# proyecto_final.net
KiCad netlist of a schematic drawn in Altium Designer
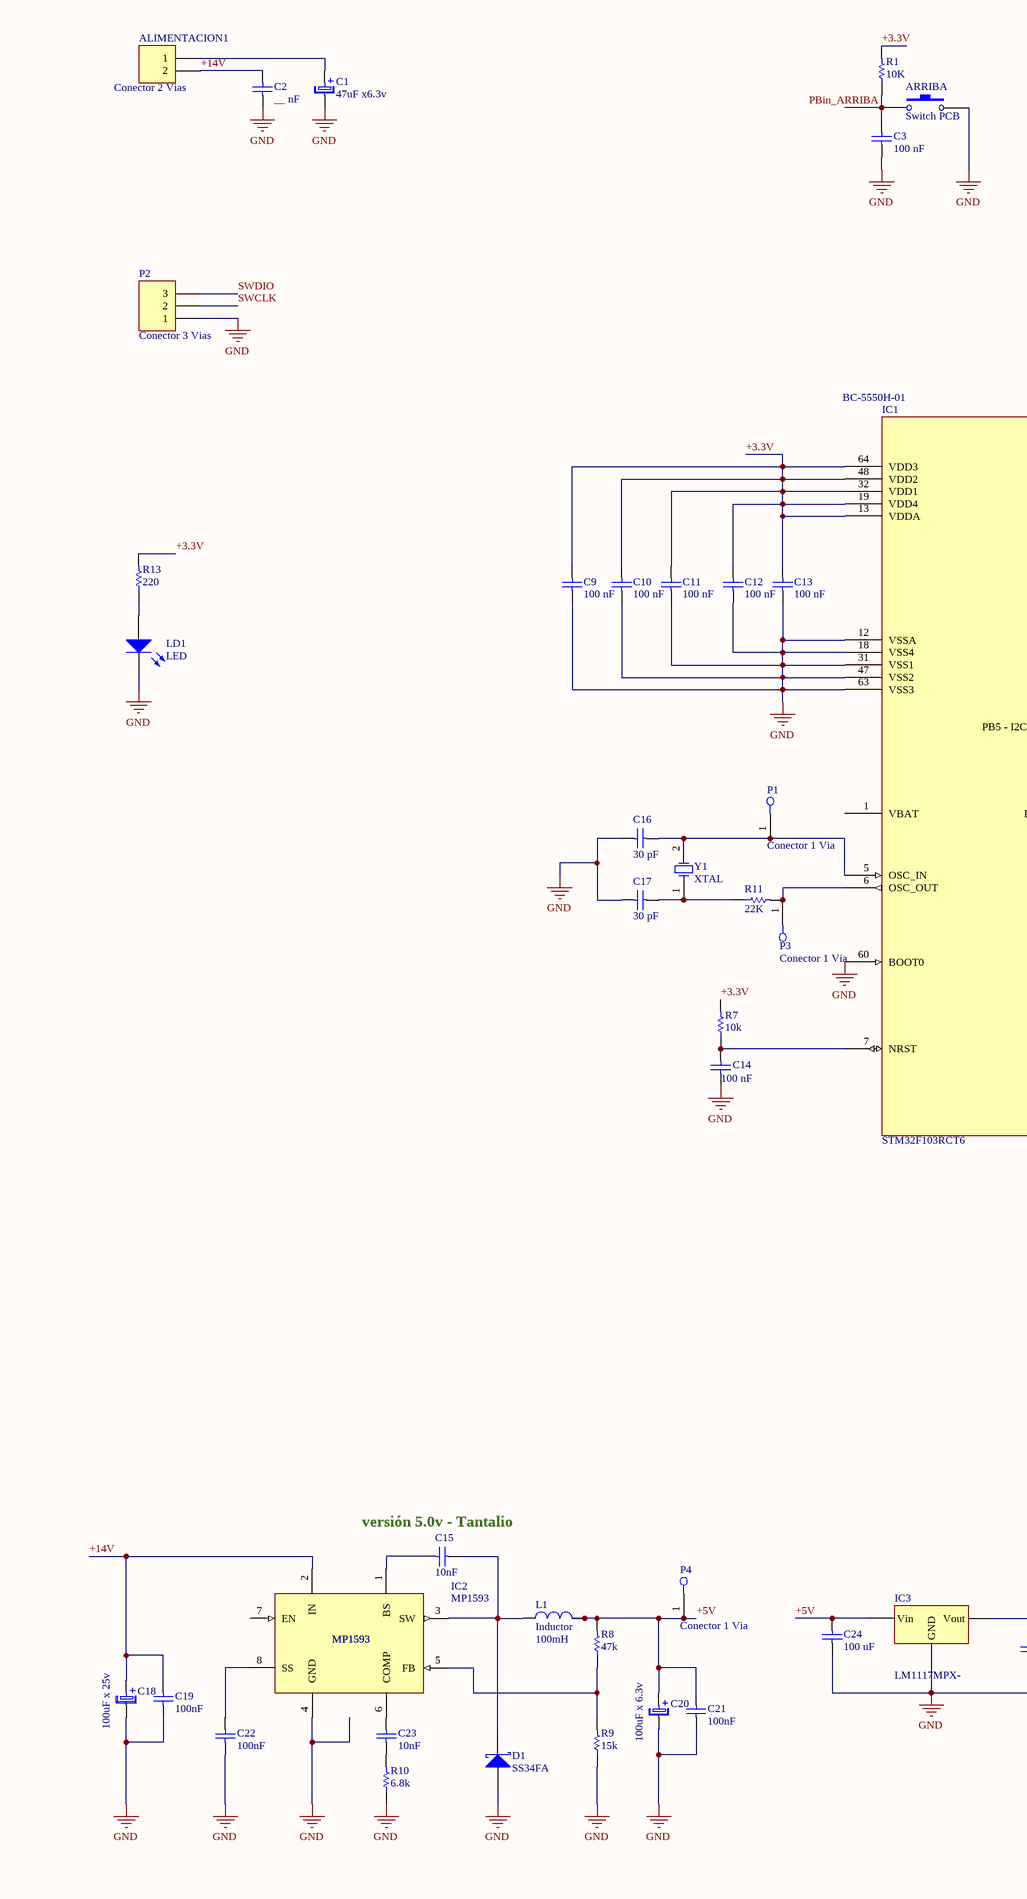
[diagram p0: proyecto final.SchDoc, left]
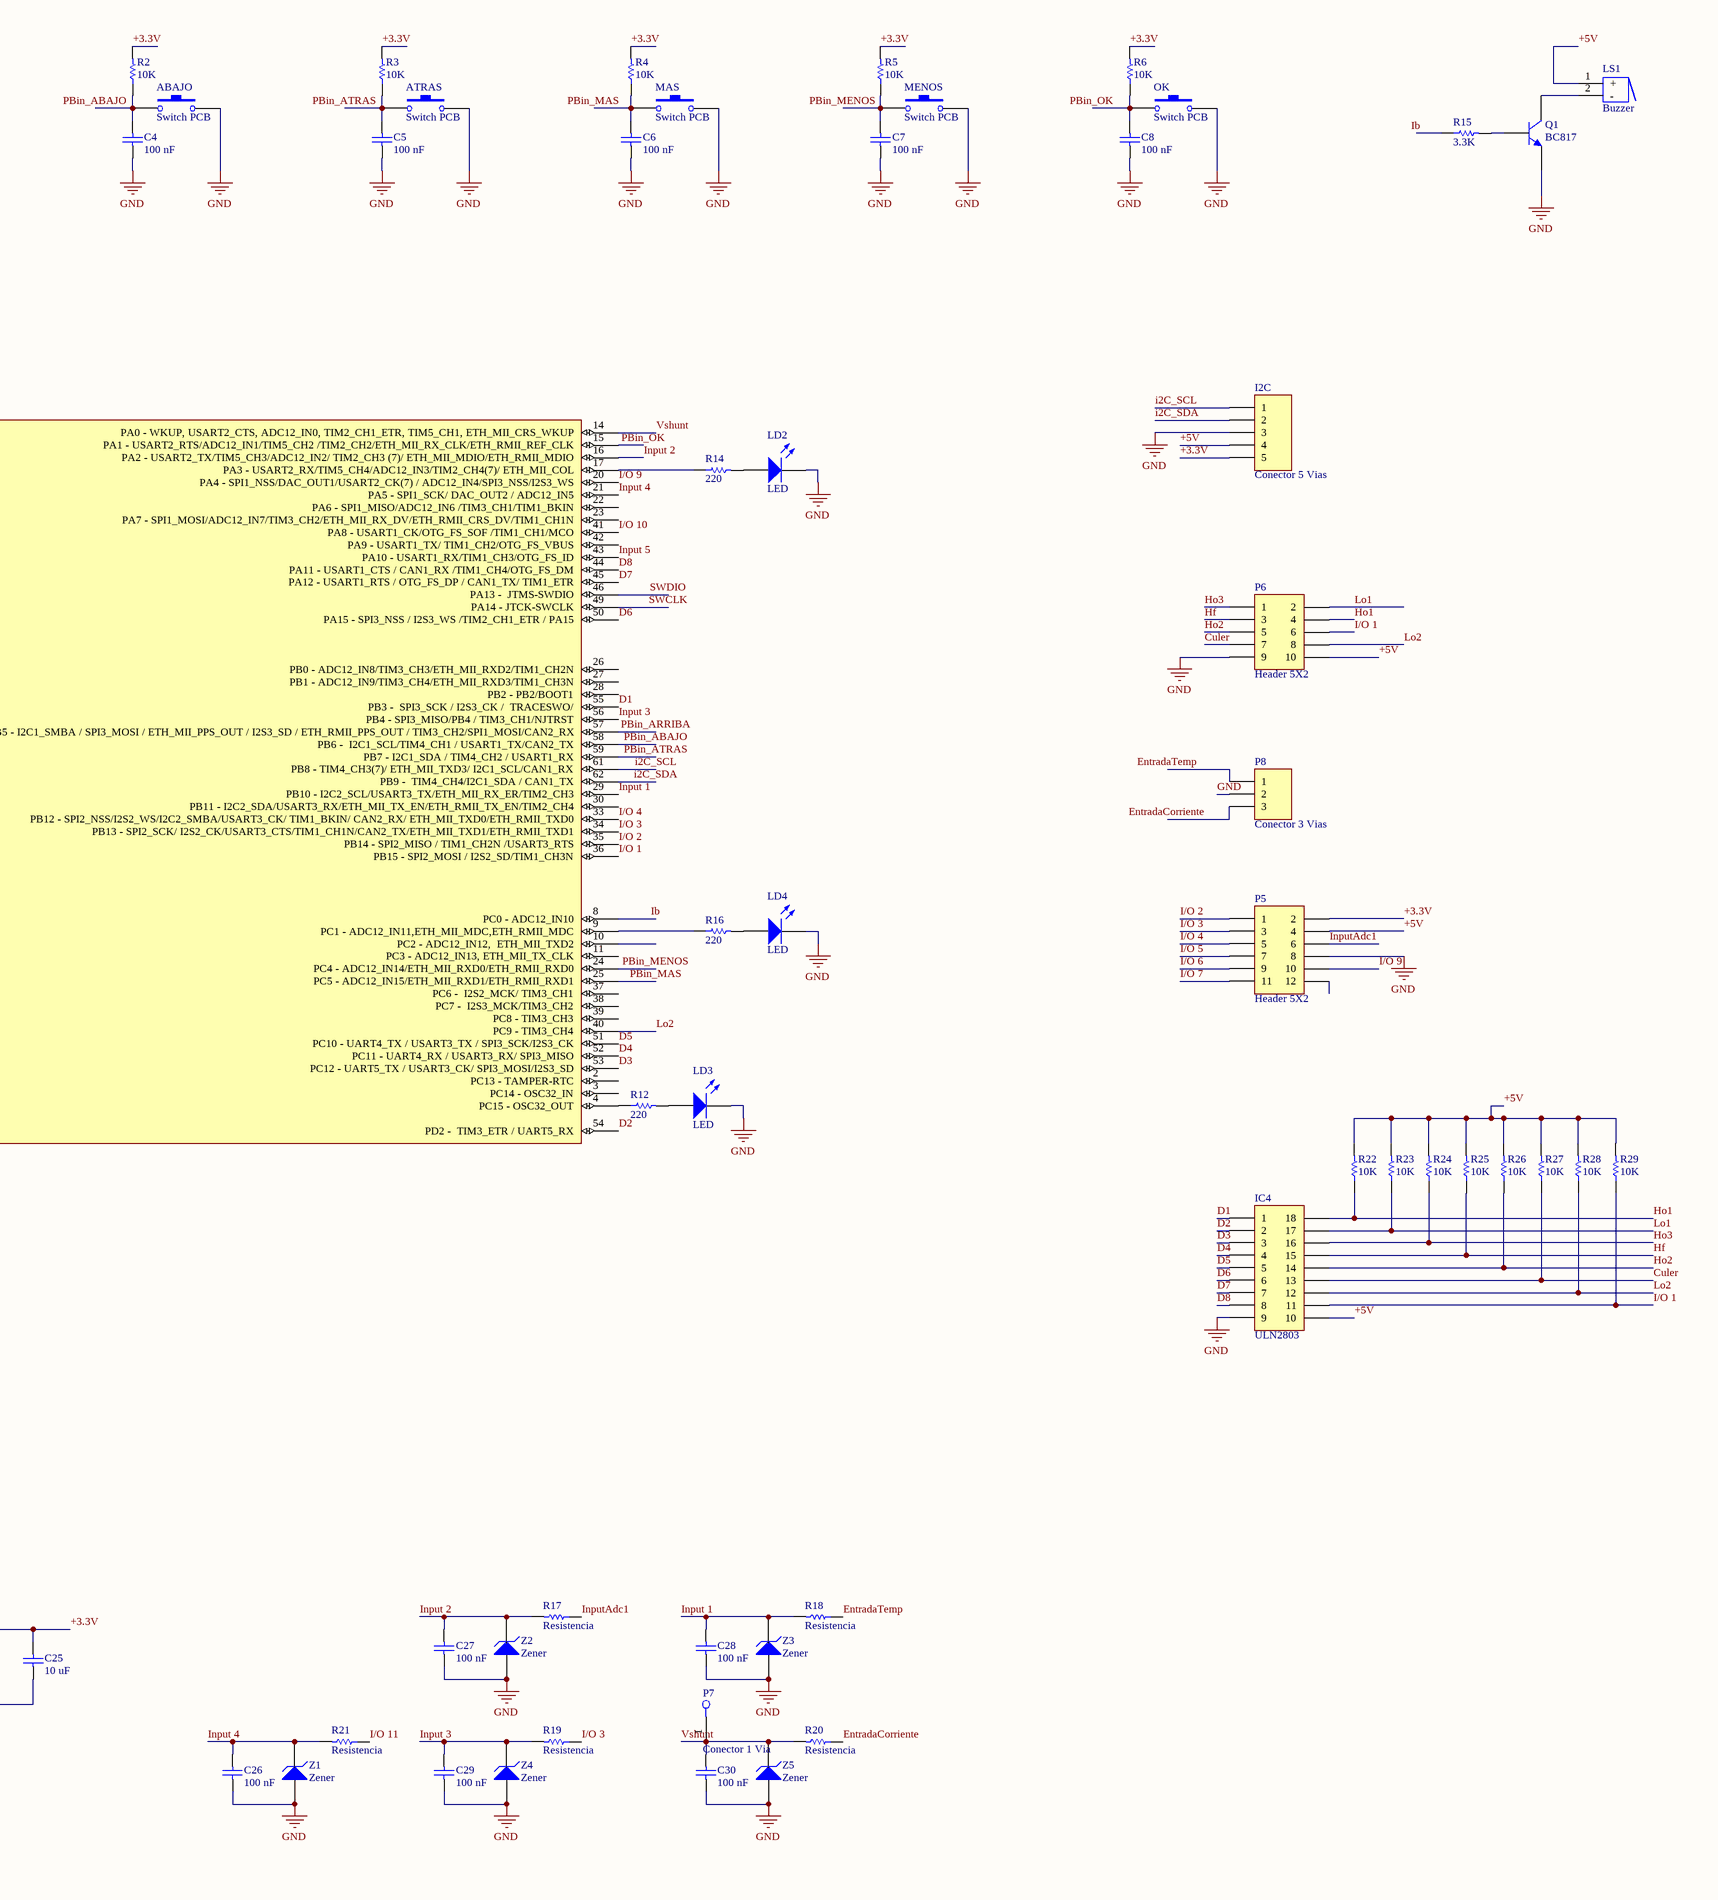
[diagram p1: proyecto final.SchDoc, right]

(export (version "E")
  (design (tool "Eeschema 10.0.6"))
  (components
    (comp (ref "ABAJO")
      (value "Switch PCB")
      (footprint "TAC SWITCH 6X6 (5MM)")
      (fields (field (name "PUBLISHER") "Altium Limited"))
      (libsource (lib "ProbIny") (part "Switch PCB"))
    )
    (comp (ref "ALIMENTACION1")
      (value "Conector 2 Vias")
      (footprint "CON 2")
      (description "Header, 2-Pin")
      (fields (field (name "PUBLISHER") "Altium Limited"))
      (libsource (lib "TORNADO LIBRERIA") (part "Header 2"))
    )
    (comp (ref "ARRIBA")
      (value "Switch PCB")
      (footprint "TAC SWITCH 6X6 (5MM)")
      (fields (field (name "PUBLISHER") "Altium Limited"))
      (libsource (lib "ProbIny") (part "Switch PCB"))
    )
    (comp (ref "ATRAS")
      (value "Switch PCB")
      (footprint "TAC SWITCH 6X6 (5MM)")
      (fields (field (name "PUBLISHER") "Altium Limited"))
      (libsource (lib "ProbIny") (part "Switch PCB"))
    )
    (comp (ref "C1")
      (value "47uF x6.3v")
      (footprint "CAP Pitch 80 - 5x11")
      (description "Capacitor Polarizado (Radial)")
      (fields (field (name "PUBLISHER") "Altium Limited"))
      (libsource (lib "TORNADO LIBRERIA") (part "Capacitor Polarizado"))
    )
    (comp (ref "C2")
      (value "__ nF")
      (footprint "C-0805")
      (description "Capacitor No Polarizado (Axial)")
      (libsource (lib "TORNADO LIBRERIA") (part "Capacitor NP"))
    )
    (comp (ref "C3")
      (value "100 nF")
      (footprint "C-0805")
      (description "Capacitor No Polarizado (Axial)")
      (libsource (lib "ProbIny") (part "Capacitor NP"))
    )
    (comp (ref "C4")
      (value "100 nF")
      (footprint "C-0805")
      (description "Capacitor No Polarizado (Axial)")
      (libsource (lib "ProbIny") (part "Capacitor NP"))
    )
    (comp (ref "C5")
      (value "100 nF")
      (footprint "C-0805")
      (description "Capacitor No Polarizado (Axial)")
      (libsource (lib "ProbIny") (part "Capacitor NP"))
    )
    (comp (ref "C6")
      (value "100 nF")
      (footprint "C-0805")
      (description "Capacitor No Polarizado (Axial)")
      (libsource (lib "ProbIny") (part "Capacitor NP"))
    )
    (comp (ref "C7")
      (value "100 nF")
      (footprint "C-0805")
      (description "Capacitor No Polarizado (Axial)")
      (libsource (lib "ProbIny") (part "Capacitor NP"))
    )
    (comp (ref "C8")
      (value "100 nF")
      (footprint "C-0805")
      (description "Capacitor No Polarizado (Axial)")
      (libsource (lib "ProbIny") (part "Capacitor NP"))
    )
    (comp (ref "C9")
      (value "100 nF")
      (footprint "C-0805")
      (description "Capacitor No Polarizado (Axial)")
      (libsource (lib "ProbIny") (part "Capacitor NP"))
    )
    (comp (ref "C10")
      (value "100 nF")
      (footprint "C-0805")
      (description "Capacitor No Polarizado (Axial)")
      (libsource (lib "ProbIny") (part "Capacitor NP"))
    )
    (comp (ref "C11")
      (value "100 nF")
      (footprint "C-0805")
      (description "Capacitor No Polarizado (Axial)")
      (libsource (lib "ProbIny") (part "Capacitor NP"))
    )
    (comp (ref "C12")
      (value "100 nF")
      (footprint "C-0805")
      (description "Capacitor No Polarizado (Axial)")
      (libsource (lib "ProbIny") (part "Capacitor NP"))
    )
    (comp (ref "C13")
      (value "100 nF")
      (footprint "C-0805")
      (description "Capacitor No Polarizado (Axial)")
      (libsource (lib "ProbIny") (part "Capacitor NP"))
    )
    (comp (ref "C14")
      (value "100 nF")
      (footprint "C-0805")
      (description "Capacitor No Polarizado (Axial)")
      (libsource (lib "TORNADO LIBRERIA") (part "Capacitor NP"))
    )
    (comp (ref "C15")
      (value "10nF")
      (footprint "C-0805")
      (description "Capacitor No Polarizado (Axial)")
      (libsource (lib "TORNADO LIBRERIA") (part "Capacitor NP"))
    )
    (comp (ref "C16")
      (value "30 pF")
      (footprint "C-0805")
      (description "Capacitor No Polarizado (Axial)")
      (libsource (lib "ProbIny") (part "Capacitor NP"))
    )
    (comp (ref "C17")
      (value "30 pF")
      (footprint "C-0805")
      (description "Capacitor No Polarizado (Axial)")
      (libsource (lib "ProbIny") (part "Capacitor NP"))
    )
    (comp (ref "C18")
      (value "100uF x 25v")
      (footprint "C-CASE-B")
      (description "Capacitor Polarizado (Radial)")
      (fields (field (name "PUBLISHER") "Altium Limited"))
      (libsource (lib "ProbIny") (part "Capacitor Polarizado"))
    )
    (comp (ref "C19")
      (value "100nF")
      (footprint "C-0805")
      (description "Capacitor No Polarizado (Axial)")
      (libsource (lib "TORNADO LIBRERIA") (part "Capacitor NP"))
    )
    (comp (ref "C20")
      (value "100uF x 6.3v")
      (footprint "C-CASE-B")
      (description "Capacitor Polarizado (Radial)")
      (fields (field (name "PUBLISHER") "Altium Limited"))
      (libsource (lib "ProbIny") (part "Capacitor Polarizado"))
    )
    (comp (ref "C21")
      (value "100nF")
      (footprint "C-0805")
      (description "Capacitor No Polarizado (Axial)")
      (libsource (lib "TORNADO LIBRERIA") (part "Capacitor NP"))
    )
    (comp (ref "C22")
      (value "100nF")
      (footprint "C-0805")
      (description "Capacitor No Polarizado (Axial)")
      (libsource (lib "TORNADO LIBRERIA") (part "Capacitor NP"))
    )
    (comp (ref "C23")
      (value "10nF")
      (footprint "C-0805")
      (description "Capacitor No Polarizado (Axial)")
      (libsource (lib "TORNADO LIBRERIA") (part "Capacitor NP"))
    )
    (comp (ref "C24")
      (value "100 uF")
      (footprint "C-0805")
      (description "Capacitor No Polarizado (Axial)")
      (libsource (lib "ProbIny") (part "Capacitor NP"))
    )
    (comp (ref "C25")
      (value "10 uF")
      (footprint "C-0805")
      (description "Capacitor No Polarizado (Axial)")
      (libsource (lib "ProbIny") (part "Capacitor NP"))
    )
    (comp (ref "C26")
      (value "100 nF")
      (footprint "C-0805")
      (description "Capacitor No Polarizado (Axial)")
      (libsource (lib "ProbIny") (part "Capacitor NP"))
    )
    (comp (ref "C27")
      (value "100 nF")
      (footprint "C-0805")
      (description "Capacitor No Polarizado (Axial)")
      (libsource (lib "ProbIny") (part "Capacitor NP"))
    )
    (comp (ref "C28")
      (value "100 nF")
      (footprint "C-0805")
      (description "Capacitor No Polarizado (Axial)")
      (libsource (lib "ProbIny") (part "Capacitor NP"))
    )
    (comp (ref "C29")
      (value "100 nF")
      (footprint "C-0805")
      (description "Capacitor No Polarizado (Axial)")
      (libsource (lib "ProbIny") (part "Capacitor NP"))
    )
    (comp (ref "C30")
      (value "100 nF")
      (footprint "C-0805")
      (description "Capacitor No Polarizado (Axial)")
      (libsource (lib "ProbIny") (part "Capacitor NP"))
    )
    (comp (ref "D1")
      (value "SS34FA")
      (footprint "SOD-123")
      (description "Diodo Schottky")
      (libsource (lib "ProbIny") (part "Diodo Schottky"))
    )
    (comp (ref "I2C")
      (value "Conector 5 Vias")
      (footprint "HEADER-V-5")
      (description "Header, 5-Pin")
      (fields (field (name "PUBLISHER") "Altium Limited"))
      (libsource (lib "ProbIny") (part "Header 5"))
    )
    (comp (ref "IC1")
      (value "STM32F103RCT6")
      (footprint "LQFP-64")
      (description "CPU M3 72MHz\r\n256k Flash\r\n2 ADC\r\n2 I2C\r\n5 USART")
      (fields (field (name "SUPPLIER PART NUMBER 1") "BC-5550H-01"))
      (libsource (lib "ProbIny") (part "STM32F103RCT6"))
    )
    (comp (ref "IC2")
      (value "MP1593")
      (footprint "SOIC-8E")
      (description "Step-Down Converter 3A, 28V, 385kHz")
      (libsource (lib "ProbIny") (part "MP1593"))
    )
    (comp (ref "IC3")
      (value "LM1117MPX-")
      (footprint "SOT-223 TERMICO")
      (libsource (lib "ProbIny") (part "LM1117MPX-"))
    )
    (comp (ref "IC4")
      (value "ULN2803")
      (footprint "SOIC-18")
      (description "Eigth darlignton array")
      (fields (field (name "PUBLISHER") "Altium Limited"))
      (libsource (lib "ProbIny") (part "ULN2803"))
    )
    (comp (ref "L1")
      (value "Inductor")
      (footprint "INDUCTOR CDRH6D28NP-100NC")
      (fields (field (name "ALTIUM_VALUE") "100mH") (field (name "PUBLISHER") "Altium Limited"))
      (libsource (lib "ProbIny") (part "Inductor"))
    )
    (comp (ref "LD1")
      (value "LED")
      (footprint "LD-0805-AZUL")
      (description "Diodo LED")
      (libsource (lib "ProbIny") (part "LED"))
    )
    (comp (ref "LD2")
      (value "LED")
      (footprint "LD-0805-AZUL")
      (description "Diodo LED")
      (libsource (lib "ProbIny") (part "LED"))
    )
    (comp (ref "LD3")
      (value "LED")
      (footprint "LD-0805-AZUL")
      (description "Diodo LED")
      (libsource (lib "ProbIny") (part "LED"))
    )
    (comp (ref "LD4")
      (value "LED")
      (footprint "LD-0805-AZUL")
      (description "Diodo LED")
      (libsource (lib "ProbIny") (part "LED"))
    )
    (comp (ref "LS1")
      (value "Buzzer")
      (footprint "BUZZER")
      (description "Magnetic Transducer Buzzer")
      (fields (field (name "PUBLISHER") "Altium Limited"))
      (libsource (lib "ProbIny") (part "Buzzer"))
    )
    (comp (ref "MAS")
      (value "Switch PCB")
      (footprint "TAC SWITCH 6X6 (5MM)")
      (fields (field (name "PUBLISHER") "Altium Limited"))
      (libsource (lib "ProbIny") (part "Switch PCB"))
    )
    (comp (ref "MENOS")
      (value "Switch PCB")
      (footprint "TAC SWITCH 6X6 (5MM)")
      (fields (field (name "PUBLISHER") "Altium Limited"))
      (libsource (lib "ProbIny") (part "Switch PCB"))
    )
    (comp (ref "OK")
      (value "Switch PCB")
      (footprint "TAC SWITCH 6X6 (5MM)")
      (fields (field (name "PUBLISHER") "Altium Limited"))
      (libsource (lib "ProbIny") (part "Switch PCB"))
    )
    (comp (ref "P1")
      (value "Conector 1 Via")
      (footprint "PAD 1.5x2.5mm")
      (description "Header, 1-Pin")
      (libsource (lib "ProbIny") (part "Header 1"))
    )
    (comp (ref "P2")
      (value "Conector 3 Vias")
      (footprint "HEADER-V-3")
      (description "Header, 3-Pin")
      (fields (field (name "PUBLISHER") "Altium Limited"))
      (libsource (lib "ProbIny") (part "Header 3"))
    )
    (comp (ref "P3")
      (value "Conector 1 Via")
      (footprint "PAD 1.5x2.5mm")
      (description "Header, 1-Pin")
      (libsource (lib "ProbIny") (part "Header 1"))
    )
    (comp (ref "P4")
      (value "Conector 1 Via")
      (footprint "PAD 1.5x2.5mm")
      (description "Header, 1-Pin")
      (libsource (lib "ProbIny") (part "Header 1"))
    )
    (comp (ref "P5")
      (value "Header 5X2")
      (footprint "HEADER 6x2")
      (description "Header, 5-Pin, Dual row")
      (fields (field (name "PUBLISHER") "Altium Limited"))
      (libsource (lib "ProbIny") (part "Header 6X2"))
    )
    (comp (ref "P6")
      (value "Header 5X2")
      (footprint "HEADER 5x2")
      (description "Header, 5-Pin, Dual row")
      (fields (field (name "PUBLISHER") "Altium Limited"))
      (libsource (lib "ProbIny") (part "Header 5X2"))
    )
    (comp (ref "P7")
      (value "Conector 1 Via")
      (footprint "PAD 1.5x2.5mm")
      (description "Header, 1-Pin")
      (libsource (lib "ProbIny") (part "Header 1"))
    )
    (comp (ref "P8")
      (value "Conector 3 Vias")
      (footprint "HEADER-V-3")
      (description "Header, 3-Pin")
      (fields (field (name "PUBLISHER") "Altium Limited"))
      (libsource (lib "") (part "Header 3_1"))
    )
    (comp (ref "Q1")
      (value "BC817")
      (footprint "SOT-23")
      (description "45 V, 500 mA NPN general-purpose transistors")
      (libsource (lib "ProbIny") (part "BC817"))
    )
    (comp (ref "R1")
      (value "10K")
      (footprint "R-0805")
      (description "Resistencia")
      (libsource (lib "ProbIny") (part "Resistencia"))
    )
    (comp (ref "R2")
      (value "10K")
      (footprint "R-0805")
      (description "Resistencia")
      (libsource (lib "ProbIny") (part "Resistencia"))
    )
    (comp (ref "R3")
      (value "10K")
      (footprint "R-0805")
      (description "Resistencia")
      (libsource (lib "ProbIny") (part "Resistencia"))
    )
    (comp (ref "R4")
      (value "10K")
      (footprint "R-0805")
      (description "Resistencia")
      (libsource (lib "ProbIny") (part "Resistencia"))
    )
    (comp (ref "R5")
      (value "10K")
      (footprint "R-0805")
      (description "Resistencia")
      (libsource (lib "ProbIny") (part "Resistencia"))
    )
    (comp (ref "R6")
      (value "10K")
      (footprint "R-0805")
      (description "Resistencia")
      (libsource (lib "ProbIny") (part "Resistencia"))
    )
    (comp (ref "R7")
      (value "10k")
      (footprint "R-0805")
      (description "Resistencia")
      (libsource (lib "TORNADO LIBRERIA") (part "Resistencia"))
    )
    (comp (ref "R8")
      (value "47k")
      (footprint "R-0805")
      (description "Resistencia")
      (libsource (lib "TORNADO LIBRERIA") (part "Resistencia"))
    )
    (comp (ref "R9")
      (value "15k")
      (footprint "R-0805")
      (description "Resistencia")
      (libsource (lib "TORNADO LIBRERIA") (part "Resistencia"))
    )
    (comp (ref "R10")
      (value "6.8k")
      (footprint "R-0805")
      (description "Resistencia")
      (libsource (lib "TORNADO LIBRERIA") (part "Resistencia"))
    )
    (comp (ref "R11")
      (value "22K")
      (footprint "R-0805")
      (description "Resistencia")
      (libsource (lib "ProbIny") (part "Resistencia"))
    )
    (comp (ref "R12")
      (value "220")
      (footprint "R-0805")
      (description "Resistencia")
      (libsource (lib "ProbIny") (part "Resistencia"))
    )
    (comp (ref "R13")
      (value "220")
      (footprint "R-0805")
      (description "Resistencia")
      (libsource (lib "ProbIny") (part "Resistencia"))
    )
    (comp (ref "R14")
      (value "220")
      (footprint "R-0805")
      (description "Resistencia")
      (libsource (lib "ProbIny") (part "Resistencia"))
    )
    (comp (ref "R15")
      (value "3.3K")
      (footprint "R-0805")
      (description "Resistencia")
      (libsource (lib "ProbIny") (part "Resistencia"))
    )
    (comp (ref "R16") (value "220") (footprint "R-0805") (libsource (lib "ProbIny") (part "Resistencia")))
    (comp (ref "R17")
      (value "Resistencia")
      (footprint "R-0805")
      (libsource (lib "ProbIny") (part "Resistencia"))
    )
    (comp (ref "R18")
      (value "Resistencia")
      (footprint "R-0805")
      (libsource (lib "ProbIny") (part "Resistencia"))
    )
    (comp (ref "R19")
      (value "Resistencia")
      (footprint "R-0805")
      (libsource (lib "ProbIny") (part "Resistencia"))
    )
    (comp (ref "R20")
      (value "Resistencia")
      (footprint "R-0805")
      (libsource (lib "ProbIny") (part "Resistencia"))
    )
    (comp (ref "R21")
      (value "Resistencia")
      (footprint "R-0805")
      (libsource (lib "ProbIny") (part "Resistencia"))
    )
    (comp (ref "R22")
      (value "10K")
      (footprint "R-0805")
      (description "Resistencia")
      (libsource (lib "ProbIny") (part "Resistencia"))
    )
    (comp (ref "R23")
      (value "10K")
      (footprint "R-0805")
      (description "Resistencia")
      (libsource (lib "ProbIny") (part "Resistencia"))
    )
    (comp (ref "R24")
      (value "10K")
      (footprint "R-0805")
      (description "Resistencia")
      (libsource (lib "ProbIny") (part "Resistencia"))
    )
    (comp (ref "R25")
      (value "10K")
      (footprint "R-0805")
      (description "Resistencia")
      (libsource (lib "ProbIny") (part "Resistencia"))
    )
    (comp (ref "R26")
      (value "10K")
      (footprint "R-0805")
      (description "Resistencia")
      (libsource (lib "ProbIny") (part "Resistencia"))
    )
    (comp (ref "R27")
      (value "10K")
      (footprint "R-0805")
      (description "Resistencia")
      (libsource (lib "ProbIny") (part "Resistencia"))
    )
    (comp (ref "R28")
      (value "10K")
      (footprint "R-0805")
      (description "Resistencia")
      (libsource (lib "ProbIny") (part "Resistencia"))
    )
    (comp (ref "R29")
      (value "10K")
      (footprint "R-0805")
      (description "Resistencia")
      (libsource (lib "ProbIny") (part "Resistencia"))
    )
    (comp (ref "Y1")
      (value "XTAL")
      (footprint "CRISTAL COMBINADO")
      (description "Crystal Oscillator")
      (fields (field (name "PUBLISHER") "Altium Limited"))
      (libsource (lib "ProbIny") (part "XTAL"))
    )
    (comp (ref "Z1")
      (value "Zener")
      (footprint "SOT-23")
      (description "Zener Diode SOT-23")
      (libsource (lib "ProbIny") (part "Diodo Zener SOT-23"))
    )
    (comp (ref "Z2")
      (value "Zener")
      (footprint "SOT-23")
      (description "Zener Diode SOT-23")
      (libsource (lib "ProbIny") (part "Diodo Zener SOT-23"))
    )
    (comp (ref "Z3")
      (value "Zener")
      (footprint "SOT-23")
      (description "Zener Diode SOT-23")
      (libsource (lib "ProbIny") (part "Diodo Zener SOT-23"))
    )
    (comp (ref "Z4")
      (value "Zener")
      (footprint "SOT-23")
      (description "Zener Diode SOT-23")
      (libsource (lib "ProbIny") (part "Diodo Zener SOT-23"))
    )
    (comp (ref "Z5")
      (value "Zener")
      (footprint "SOT-23")
      (description "Zener Diode SOT-23")
      (libsource (lib "ProbIny") (part "Diodo Zener SOT-23"))
    )
  )
  (nets
    (net (code "1") (name "/+3.3V") (class "Default")
      (node (ref "C10") (pin "2") (pinfunction "2_2") (pintype "passive"))
      (node (ref "C11") (pin "2") (pinfunction "2_2") (pintype "passive"))
      (node (ref "C12") (pin "2") (pinfunction "2_2") (pintype "passive"))
      (node (ref "C13") (pin "2") (pinfunction "2_2") (pintype "passive"))
      (node (ref "C25") (pin "1") (pinfunction "1_1") (pintype "passive"))
      (node (ref "C9") (pin "2") (pinfunction "2_2") (pintype "passive"))
      (node (ref "I2C") (pin "5") (pinfunction "5_5") (pintype "passive"))
      (node (ref "IC1") (pin "13") (pinfunction "VDDA_13") (pintype "power_in"))
      (node (ref "IC1") (pin "19") (pinfunction "VDD4_19") (pintype "power_in"))
      (node (ref "IC1") (pin "32") (pinfunction "VDD1_32") (pintype "power_in"))
      (node (ref "IC1") (pin "48") (pinfunction "VDD2_48") (pintype "power_in"))
      (node (ref "IC1") (pin "64") (pinfunction "VDD3_64") (pintype "power_in"))
      (node (ref "IC3") (pin "2") (pinfunction "Vout_2") (pintype "passive"))
      (node (ref "P5") (pin "2") (pinfunction "2_2") (pintype "passive"))
      (node (ref "R1") (pin "2") (pinfunction "2_2") (pintype "passive"))
      (node (ref "R13") (pin "2") (pinfunction "2_2") (pintype "passive"))
      (node (ref "R2") (pin "2") (pinfunction "2_2") (pintype "passive"))
      (node (ref "R3") (pin "2") (pinfunction "2_2") (pintype "passive"))
      (node (ref "R4") (pin "2") (pinfunction "2_2") (pintype "passive"))
      (node (ref "R5") (pin "2") (pinfunction "2_2") (pintype "passive"))
      (node (ref "R6") (pin "2") (pinfunction "2_2") (pintype "passive"))
      (node (ref "R7") (pin "2") (pinfunction "2_2") (pintype "passive"))
    )
    (net (code "2") (name "/+5V") (class "Default")
      (node (ref "C20") (pin "1") (pinfunction "1_1") (pintype "passive"))
      (node (ref "C21") (pin "2") (pinfunction "2_2") (pintype "passive"))
      (node (ref "C24") (pin "1") (pinfunction "1_1") (pintype "passive"))
      (node (ref "I2C") (pin "4") (pinfunction "4_4") (pintype "passive"))
      (node (ref "IC3") (pin "3") (pinfunction "Vin_3") (pintype "passive"))
      (node (ref "IC4") (pin "10") (pinfunction "10_10") (pintype "passive"))
      (node (ref "L1") (pin "2") (pinfunction "2_2") (pintype "passive"))
      (node (ref "LS1") (pin "1") (pinfunction "+_1") (pintype "passive"))
      (node (ref "P4") (pin "1") (pinfunction "1_1") (pintype "passive"))
      (node (ref "P5") (pin "4") (pinfunction "4_4") (pintype "passive"))
      (node (ref "P6") (pin "10") (pinfunction "10_10") (pintype "passive"))
      (node (ref "R22") (pin "2") (pinfunction "2_2") (pintype "passive"))
      (node (ref "R23") (pin "2") (pinfunction "2_2") (pintype "passive"))
      (node (ref "R24") (pin "2") (pinfunction "2_2") (pintype "passive"))
      (node (ref "R25") (pin "2") (pinfunction "2_2") (pintype "passive"))
      (node (ref "R26") (pin "2") (pinfunction "2_2") (pintype "passive"))
      (node (ref "R27") (pin "2") (pinfunction "2_2") (pintype "passive"))
      (node (ref "R28") (pin "2") (pinfunction "2_2") (pintype "passive"))
      (node (ref "R29") (pin "2") (pinfunction "2_2") (pintype "passive"))
      (node (ref "R8") (pin "2") (pinfunction "2_2") (pintype "passive"))
    )
    (net (code "3") (name "/+14V") (class "Default")
      (node (ref "ALIMENTACION1") (pin "2") (pinfunction "2_2") (pintype "passive"))
      (node (ref "C18") (pin "1") (pinfunction "1_1") (pintype "passive"))
      (node (ref "C19") (pin "2") (pinfunction "2_2") (pintype "passive"))
      (node (ref "C2") (pin "2") (pinfunction "2_2") (pintype "passive"))
      (node (ref "IC2") (pin "2") (pinfunction "IN_2") (pintype "power_in"))
    )
    (net (code "5") (name "/Culer") (class "Default")
      (node (ref "IC4") (pin "13") (pinfunction "13_13") (pintype "passive"))
      (node (ref "P6") (pin "7") (pinfunction "7_7") (pintype "passive"))
      (node (ref "R27") (pin "1") (pinfunction "1_1") (pintype "passive"))
    )
    (net (code "6") (name "/D1") (class "Default")
      (node (ref "IC1") (pin "55") (pinfunction "PB3_-__SPI3_SCK_/_I2S3_CK_/__TRACESWO/_55") (pintype "bidirectional"))
      (node (ref "IC4") (pin "1") (pinfunction "1_1") (pintype "passive"))
    )
    (net (code "7") (name "/D2") (class "Default")
      (node (ref "IC1") (pin "54") (pinfunction "PD2_-__TIM3_ETR_/_UART5_RX_54") (pintype "bidirectional"))
      (node (ref "IC4") (pin "2") (pinfunction "2_2") (pintype "passive"))
    )
    (net (code "8") (name "/D3") (class "Default")
      (node (ref "IC1") (pin "53") (pinfunction "PC12_-_UART5_TX_/_USART3_CK/_SPI3_MOSI/I2S3_SD_53") (pintype "bidirectional"))
      (node (ref "IC4") (pin "3") (pinfunction "3_3") (pintype "passive"))
    )
    (net (code "9") (name "/D4") (class "Default")
      (node (ref "IC1") (pin "52") (pinfunction "PC11_-_UART4_RX_/_USART3_RX/_SPI3_MISO_52") (pintype "bidirectional"))
      (node (ref "IC4") (pin "4") (pinfunction "4_4") (pintype "passive"))
    )
    (net (code "10") (name "/D5") (class "Default")
      (node (ref "IC1") (pin "51") (pinfunction "PC10_-_UART4_TX_/_USART3_TX_/_SPI3_SCK/I2S3_CK_51") (pintype "bidirectional"))
      (node (ref "IC4") (pin "5") (pinfunction "5_5") (pintype "passive"))
    )
    (net (code "11") (name "/D6") (class "Default")
      (node (ref "IC1") (pin "50") (pinfunction "PA15_-_SPI3_NSS_/_I2S3_WS_/TIM2_CH1_ETR_/_PA15_50") (pintype "bidirectional"))
      (node (ref "IC4") (pin "6") (pinfunction "6_6") (pintype "passive"))
    )
    (net (code "12") (name "/D7") (class "Default")
      (node (ref "IC1") (pin "45") (pinfunction "PA12_-_USART1_RTS_/_OTG_FS_DP_/_CAN1_TX/_TIM1_ETR_45") (pintype "bidirectional"))
      (node (ref "IC4") (pin "7") (pinfunction "7_7") (pintype "passive"))
    )
    (net (code "13") (name "/D8") (class "Default")
      (node (ref "IC1") (pin "44") (pinfunction "PA11_-_USART1_CTS_/_CAN1_RX_/TIM1_CH4/OTG_FS_DM_44") (pintype "bidirectional"))
      (node (ref "IC4") (pin "8") (pinfunction "8_8") (pintype "passive"))
    )
    (net (code "14") (name "/EntradaCorriente") (class "Default")
      (node (ref "P8") (pin "3") (pinfunction "3_3") (pintype "passive"))
      (node (ref "R20") (pin "1") (pinfunction "1_1") (pintype "passive"))
    )
    (net (code "15") (name "/EntradaTemp") (class "Default")
      (node (ref "P8") (pin "1") (pinfunction "1_1") (pintype "passive"))
      (node (ref "R18") (pin "1") (pinfunction "1_1") (pintype "passive"))
    )
    (net (code "16") (name "/Hf") (class "Default")
      (node (ref "IC4") (pin "15") (pinfunction "15_15") (pintype "passive"))
      (node (ref "P6") (pin "3") (pinfunction "3_3") (pintype "passive"))
      (node (ref "R25") (pin "1") (pinfunction "1_1") (pintype "passive"))
    )
    (net (code "17") (name "/Ho1") (class "Default")
      (node (ref "IC4") (pin "18") (pinfunction "18_18") (pintype "passive"))
      (node (ref "P6") (pin "4") (pinfunction "4_4") (pintype "passive"))
      (node (ref "R22") (pin "1") (pinfunction "1_1") (pintype "passive"))
    )
    (net (code "18") (name "/Ho2") (class "Default")
      (node (ref "IC4") (pin "14") (pinfunction "14_14") (pintype "passive"))
      (node (ref "P6") (pin "5") (pinfunction "5_5") (pintype "passive"))
      (node (ref "R26") (pin "1") (pinfunction "1_1") (pintype "passive"))
    )
    (net (code "19") (name "/Ho3") (class "Default")
      (node (ref "IC4") (pin "16") (pinfunction "16_16") (pintype "passive"))
      (node (ref "P6") (pin "1") (pinfunction "1_1") (pintype "passive"))
      (node (ref "R24") (pin "1") (pinfunction "1_1") (pintype "passive"))
    )
    (net (code "20") (name "/Ib") (class "Default")
      (node (ref "IC1") (pin "8") (pinfunction "PC0_-_ADC12_IN10_8") (pintype "bidirectional"))
      (node (ref "R15") (pin "1") (pinfunction "1_1") (pintype "passive"))
    )
    (net (code "21") (name "/Input 1") (class "Default")
      (node (ref "C28") (pin "2") (pinfunction "2_2") (pintype "passive"))
      (node (ref "IC1") (pin "29") (pinfunction "PB10_-_I2C2_SCL/USART3_TX/ETH_MII_RX_ER/TIM2_CH3_29") (pintype "bidirectional"))
      (node (ref "R18") (pin "2") (pinfunction "2_2") (pintype "passive"))
      (node (ref "Z3") (pin "3") (pinfunction "K_3") (pintype "passive"))
    )
    (net (code "22") (name "/Input 2") (class "Default")
      (node (ref "C27") (pin "2") (pinfunction "2_2") (pintype "passive"))
      (node (ref "IC1") (pin "16") (pinfunction "PA2_-_USART2_TX/TIM5_CH3/ADC12_IN2/_TIM2_CH3_(7)/_ETH_MII_MDIO/ETH_RMII_MDIO_16") (pintype "bidirectional"))
      (node (ref "R17") (pin "2") (pinfunction "2_2") (pintype "passive"))
      (node (ref "Z2") (pin "3") (pinfunction "K_3") (pintype "passive"))
    )
    (net (code "23") (name "/Input 3") (class "Default")
      (node (ref "C29") (pin "2") (pinfunction "2_2") (pintype "passive"))
      (node (ref "IC1") (pin "56") (pinfunction "PB4_-_SPI3_MISO/PB4_/_TIM3_CH1/NJTRST_56") (pintype "bidirectional"))
      (node (ref "R19") (pin "2") (pinfunction "2_2") (pintype "passive"))
      (node (ref "Z4") (pin "3") (pinfunction "K_3") (pintype "passive"))
    )
    (net (code "24") (name "/Input 4") (class "Default")
      (node (ref "C26") (pin "2") (pinfunction "2_2") (pintype "passive"))
      (node (ref "IC1") (pin "21") (pinfunction "PA5_-_SPI1_SCK/_DAC_OUT2_/_ADC12_IN5_21") (pintype "bidirectional"))
      (node (ref "R21") (pin "2") (pinfunction "2_2") (pintype "passive"))
      (node (ref "Z1") (pin "3") (pinfunction "K_3") (pintype "passive"))
    )
    (net (code "25") (name "/Input 5") (class "Default")
      (node (ref "IC1") (pin "43") (pinfunction "PA10_-_USART1_RX/TIM1_CH3/OTG_FS_ID_43") (pintype "bidirectional"))
    )
    (net (code "26") (name "/InputAdc1") (class "Default")
      (node (ref "P5") (pin "6") (pinfunction "6_6") (pintype "passive"))
      (node (ref "R17") (pin "1") (pinfunction "1_1") (pintype "passive"))
    )
    (net (code "27") (name "/I{slash}O 1") (class "Default")
      (node (ref "IC1") (pin "36") (pinfunction "PB15_-_SPI2_MOSI_/_I2S2_SD/TIM1_CH3N_36") (pintype "bidirectional"))
      (node (ref "IC4") (pin "11") (pinfunction "11_11") (pintype "passive"))
      (node (ref "P6") (pin "6") (pinfunction "6_6") (pintype "passive"))
      (node (ref "R29") (pin "1") (pinfunction "1_1") (pintype "passive"))
    )
    (net (code "28") (name "/I{slash}O 2") (class "Default")
      (node (ref "IC1") (pin "35") (pinfunction "PB14_-_SPI2_MISO_/_TIM1_CH2N_/USART3_RTS_35") (pintype "bidirectional"))
      (node (ref "P5") (pin "1") (pinfunction "1_1") (pintype "passive"))
    )
    (net (code "29") (name "/I{slash}O 3") (class "Default")
      (node (ref "IC1") (pin "34") (pinfunction "PB13_-_SPI2_SCK/_I2S2_CK/USART3_CTS/TIM1_CH1N/CAN2_TX/ETH_MII_TXD1/ETH_RMII_TXD1_34") (pintype "bidirectional"))
      (node (ref "P5") (pin "3") (pinfunction "3_3") (pintype "passive"))
      (node (ref "R19") (pin "1") (pinfunction "1_1") (pintype "passive"))
    )
    (net (code "30") (name "/I{slash}O 4") (class "Default")
      (node (ref "IC1") (pin "33") (pinfunction "PB12_-_SPI2_NSS/I2S2_WS/I2C2_SMBA/USART3_CK/_TIM1_BKIN/_CAN2_RX/_ETH_MII_TXD0/ETH_RMII_TXD0_33") (pintype "bidirectional"))
      (node (ref "P5") (pin "5") (pinfunction "5_5") (pintype "passive"))
    )
    (net (code "31") (name "/I{slash}O 5") (class "Default")
      (node (ref "P5") (pin "7") (pinfunction "7_7") (pintype "passive"))
    )
    (net (code "32") (name "/I{slash}O 6") (class "Default")
      (node (ref "P5") (pin "9") (pinfunction "9_9") (pintype "passive"))
    )
    (net (code "33") (name "/I{slash}O 7") (class "Default")
      (node (ref "P5") (pin "11") (pinfunction "11_11") (pintype "passive"))
    )
    (net (code "34") (name "/I{slash}O 9") (class "Default")
      (node (ref "IC1") (pin "20") (pinfunction "PA4_-_SPI1_NSS/DAC_OUT1/USART2_CK(7)_/_ADC12_IN4/SPI3_NSS/I2S3_WS_20") (pintype "bidirectional"))
      (node (ref "P5") (pin "10") (pinfunction "10_10") (pintype "passive"))
    )
    (net (code "35") (name "/I{slash}O 10") (class "Default")
      (node (ref "IC1") (pin "41") (pinfunction "PA8_-_USART1_CK/OTG_FS_SOF_/TIM1_CH1/MCO_41") (pintype "bidirectional"))
    )
    (net (code "36") (name "/I{slash}O 11") (class "Default")
      (node (ref "R21") (pin "1") (pinfunction "1_1") (pintype "passive"))
    )
    (net (code "37") (name "/Lo1") (class "Default")
      (node (ref "IC4") (pin "17") (pinfunction "17_17") (pintype "passive"))
      (node (ref "P6") (pin "2") (pinfunction "2_2") (pintype "passive"))
      (node (ref "R23") (pin "1") (pinfunction "1_1") (pintype "passive"))
    )
    (net (code "38") (name "/Lo2") (class "Default")
      (node (ref "IC1") (pin "40") (pinfunction "PC9_-_TIM3_CH4_40") (pintype "bidirectional"))
      (node (ref "IC4") (pin "12") (pinfunction "12_12") (pintype "passive"))
      (node (ref "P6") (pin "8") (pinfunction "8_8") (pintype "passive"))
      (node (ref "R28") (pin "1") (pinfunction "1_1") (pintype "passive"))
    )
    (net (code "39") (name "/PBin_ABAJO") (class "Default")
      (node (ref "ABAJO") (pin "1") (pinfunction "1_1") (pintype "passive"))
      (node (ref "C4") (pin "2") (pinfunction "2_2") (pintype "passive"))
      (node (ref "IC1") (pin "58") (pinfunction "PB6_-__I2C1_SCL/TIM4_CH1_/_USART1_TX/CAN2_TX_58") (pintype "bidirectional"))
      (node (ref "R2") (pin "1") (pinfunction "1_1") (pintype "passive"))
    )
    (net (code "40") (name "/PBin_ARRIBA") (class "Default")
      (node (ref "ARRIBA") (pin "1") (pinfunction "1_1") (pintype "passive"))
      (node (ref "C3") (pin "2") (pinfunction "2_2") (pintype "passive"))
      (node (ref "IC1") (pin "57") (pinfunction "PB5_-_I2C1_SMBA_/_SPI3_MOSI_/_ETH_MII_PPS_OUT_/_I2S3_SD_/_ETH_RMII_PPS_OUT_/_TIM3_CH2/SPI1_MOSI/CAN2_RX_57") (pintype "bidirectional"))
      (node (ref "R1") (pin "1") (pinfunction "1_1") (pintype "passive"))
    )
    (net (code "41") (name "/PBin_ATRAS") (class "Default")
      (node (ref "ATRAS") (pin "1") (pinfunction "1_1") (pintype "passive"))
      (node (ref "C5") (pin "2") (pinfunction "2_2") (pintype "passive"))
      (node (ref "IC1") (pin "59") (pinfunction "PB7_-_I2C1_SDA_/_TIM4_CH2_/_USART1_RX_59") (pintype "bidirectional"))
      (node (ref "R3") (pin "1") (pinfunction "1_1") (pintype "passive"))
    )
    (net (code "42") (name "/PBin_MAS") (class "Default")
      (node (ref "C6") (pin "2") (pinfunction "2_2") (pintype "passive"))
      (node (ref "IC1") (pin "25") (pinfunction "PC5_-_ADC12_IN15/ETH_MII_RXD1/ETH_RMII_RXD1_25") (pintype "bidirectional"))
      (node (ref "MAS") (pin "1") (pinfunction "1_1") (pintype "passive"))
      (node (ref "R4") (pin "1") (pinfunction "1_1") (pintype "passive"))
    )
    (net (code "43") (name "/PBin_MENOS") (class "Default")
      (node (ref "C7") (pin "2") (pinfunction "2_2") (pintype "passive"))
      (node (ref "IC1") (pin "24") (pinfunction "PC4_-_ADC12_IN14/ETH_MII_RXD0/ETH_RMII_RXD0_24") (pintype "bidirectional"))
      (node (ref "MENOS") (pin "1") (pinfunction "1_1") (pintype "passive"))
      (node (ref "R5") (pin "1") (pinfunction "1_1") (pintype "passive"))
    )
    (net (code "44") (name "/PBin_OK") (class "Default")
      (node (ref "C8") (pin "2") (pinfunction "2_2") (pintype "passive"))
      (node (ref "IC1") (pin "15") (pinfunction "PA1_-_USART2_RTS/ADC12_IN1/TIM5_CH2_/TIM2_CH2/ETH_MII_RX_CLK/ETH_RMII_REF_CLK_15") (pintype "bidirectional"))
      (node (ref "OK") (pin "1") (pinfunction "1_1") (pintype "passive"))
      (node (ref "R6") (pin "1") (pinfunction "1_1") (pintype "passive"))
    )
    (net (code "45") (name "/SWCLK") (class "Default")
      (node (ref "IC1") (pin "49") (pinfunction "PA14_-_JTCK-SWCLK_49") (pintype "bidirectional"))
      (node (ref "P2") (pin "2") (pinfunction "2_2") (pintype "passive"))
    )
    (net (code "46") (name "/SWDIO") (class "Default")
      (node (ref "IC1") (pin "46") (pinfunction "PA13_-__JTMS-SWDIO_46") (pintype "bidirectional"))
      (node (ref "P2") (pin "3") (pinfunction "3_3") (pintype "passive"))
    )
    (net (code "47") (name "/Vshunt") (class "Default")
      (node (ref "C30") (pin "2") (pinfunction "2_2") (pintype "passive"))
      (node (ref "IC1") (pin "14") (pinfunction "PA0_-_WKUP,_USART2_CTS,_ADC12_IN0,_TIM2_CH1_ETR,_TIM5_CH1,_ETH_MII_CRS_WKUP_14") (pintype "bidirectional"))
      (node (ref "P7") (pin "1") (pinfunction "1_1") (pintype "passive"))
      (node (ref "R20") (pin "2") (pinfunction "2_2") (pintype "passive"))
      (node (ref "Z5") (pin "3") (pinfunction "K_3") (pintype "passive"))
    )
    (net (code "48") (name "/i2C_SCL") (class "Default")
      (node (ref "I2C") (pin "1") (pinfunction "1_1") (pintype "passive"))
      (node (ref "IC1") (pin "61") (pinfunction "PB8_-_TIM4_CH3(7)/_ETH_MII_TXD3/_I2C1_SCL/CAN1_RX_61") (pintype "bidirectional"))
    )
    (net (code "49") (name "/i2C_SDA") (class "Default")
      (node (ref "I2C") (pin "2") (pinfunction "2_2") (pintype "passive"))
      (node (ref "IC1") (pin "62") (pinfunction "PB9_-__TIM4_CH4/I2C1_SDA_/_CAN1_TX_62") (pintype "bidirectional"))
    )
    (net (code "50") (name "GND") (class "Default")
      (node (ref "ABAJO") (pin "2") (pinfunction "2_2") (pintype "passive"))
      (node (ref "ARRIBA") (pin "2") (pinfunction "2_2") (pintype "passive"))
      (node (ref "ATRAS") (pin "2") (pinfunction "2_2") (pintype "passive"))
      (node (ref "C1") (pin "2") (pinfunction "2_2") (pintype "passive"))
      (node (ref "C10") (pin "1") (pinfunction "1_1") (pintype "passive"))
      (node (ref "C11") (pin "1") (pinfunction "1_1") (pintype "passive"))
      (node (ref "C12") (pin "1") (pinfunction "1_1") (pintype "passive"))
      (node (ref "C13") (pin "1") (pinfunction "1_1") (pintype "passive"))
      (node (ref "C14") (pin "1") (pinfunction "1_1") (pintype "passive"))
      (node (ref "C16") (pin "2") (pinfunction "2_2") (pintype "passive"))
      (node (ref "C17") (pin "2") (pinfunction "2_2") (pintype "passive"))
      (node (ref "C18") (pin "2") (pinfunction "2_2") (pintype "passive"))
      (node (ref "C19") (pin "1") (pinfunction "1_1") (pintype "passive"))
      (node (ref "C2") (pin "1") (pinfunction "1_1") (pintype "passive"))
      (node (ref "C20") (pin "2") (pinfunction "2_2") (pintype "passive"))
      (node (ref "C21") (pin "1") (pinfunction "1_1") (pintype "passive"))
      (node (ref "C22") (pin "1") (pinfunction "1_1") (pintype "passive"))
      (node (ref "C24") (pin "2") (pinfunction "2_2") (pintype "passive"))
      (node (ref "C25") (pin "2") (pinfunction "2_2") (pintype "passive"))
      (node (ref "C26") (pin "1") (pinfunction "1_1") (pintype "passive"))
      (node (ref "C27") (pin "1") (pinfunction "1_1") (pintype "passive"))
      (node (ref "C28") (pin "1") (pinfunction "1_1") (pintype "passive"))
      (node (ref "C29") (pin "1") (pinfunction "1_1") (pintype "passive"))
      (node (ref "C3") (pin "1") (pinfunction "1_1") (pintype "passive"))
      (node (ref "C30") (pin "1") (pinfunction "1_1") (pintype "passive"))
      (node (ref "C4") (pin "1") (pinfunction "1_1") (pintype "passive"))
      (node (ref "C5") (pin "1") (pinfunction "1_1") (pintype "passive"))
      (node (ref "C6") (pin "1") (pinfunction "1_1") (pintype "passive"))
      (node (ref "C7") (pin "1") (pinfunction "1_1") (pintype "passive"))
      (node (ref "C8") (pin "1") (pinfunction "1_1") (pintype "passive"))
      (node (ref "C9") (pin "1") (pinfunction "1_1") (pintype "passive"))
      (node (ref "D1") (pin "1") (pinfunction "A_1") (pintype "passive"))
      (node (ref "I2C") (pin "3") (pinfunction "3_3") (pintype "passive"))
      (node (ref "IC1") (pin "12") (pinfunction "VSSA_12") (pintype "power_in"))
      (node (ref "IC1") (pin "18") (pinfunction "VSS4_18") (pintype "power_in"))
      (node (ref "IC1") (pin "31") (pinfunction "VSS1_31") (pintype "power_in"))
      (node (ref "IC1") (pin "47") (pinfunction "VSS2_47") (pintype "power_in"))
      (node (ref "IC1") (pin "60") (pinfunction "BOOT0_60") (pintype "input"))
      (node (ref "IC1") (pin "63") (pinfunction "VSS3_63") (pintype "power_in"))
      (node (ref "IC2") (pin "4") (pinfunction "GND_4") (pintype "power_in"))
      (node (ref "IC3") (pin "1") (pinfunction "GND_1") (pintype "passive"))
      (node (ref "IC4") (pin "9") (pinfunction "9_9") (pintype "passive"))
      (node (ref "LD1") (pin "2") (pinfunction "K_2") (pintype "passive"))
      (node (ref "LD2") (pin "2") (pinfunction "K_2") (pintype "passive"))
      (node (ref "LD3") (pin "2") (pinfunction "K_2") (pintype "passive"))
      (node (ref "LD4") (pin "2") (pinfunction "K_2") (pintype "passive"))
      (node (ref "MAS") (pin "2") (pinfunction "2_2") (pintype "passive"))
      (node (ref "MENOS") (pin "2") (pinfunction "2_2") (pintype "passive"))
      (node (ref "OK") (pin "2") (pinfunction "2_2") (pintype "passive"))
      (node (ref "P2") (pin "1") (pinfunction "1_1") (pintype "passive"))
      (node (ref "P5") (pin "8") (pinfunction "8_8") (pintype "passive"))
      (node (ref "P6") (pin "9") (pinfunction "9_9") (pintype "passive"))
      (node (ref "P8") (pin "2") (pinfunction "2_2") (pintype "passive"))
      (node (ref "Q1") (pin "2") (pinfunction "E_2") (pintype "passive"))
      (node (ref "R10") (pin "1") (pinfunction "1_1") (pintype "passive"))
      (node (ref "R9") (pin "1") (pinfunction "1_1") (pintype "passive"))
      (node (ref "Z1") (pin "1") (pinfunction "A_1") (pintype "passive"))
      (node (ref "Z2") (pin "1") (pinfunction "A_1") (pintype "passive"))
      (node (ref "Z3") (pin "1") (pinfunction "A_1") (pintype "passive"))
      (node (ref "Z4") (pin "1") (pinfunction "A_1") (pintype "passive"))
      (node (ref "Z5") (pin "1") (pinfunction "A_1") (pintype "passive"))
    )
    (net (code "51") (name "Net-(ALIMENTACION1-Pad1)") (class "Default")
      (node (ref "ALIMENTACION1") (pin "1") (pinfunction "1_1") (pintype "passive"))
      (node (ref "C1") (pin "1") (pinfunction "1_1") (pintype "passive"))
    )
    (net (code "52") (name "Net-(C23-Pad1)") (class "Default")
      (node (ref "C23") (pin "1") (pinfunction "1_1") (pintype "passive"))
      (node (ref "R10") (pin "2") (pinfunction "2_2") (pintype "passive"))
    )
    (net (code "53") (name "Net-(D1-K)") (class "Default")
      (node (ref "C15") (pin "2") (pinfunction "2_2") (pintype "passive"))
      (node (ref "D1") (pin "2") (pinfunction "K_2") (pintype "passive"))
      (node (ref "IC2") (pin "3") (pinfunction "SW_3") (pintype "output"))
      (node (ref "L1") (pin "1") (pinfunction "1_1") (pintype "passive"))
    )
    (net (code "54") (name "Net-(IC1-NRST)") (class "Default")
      (node (ref "C14") (pin "2") (pinfunction "2_2") (pintype "passive"))
      (node (ref "IC1") (pin "7") (pinfunction "NRST_7") (pintype "bidirectional"))
      (node (ref "R7") (pin "1") (pinfunction "1_1") (pintype "passive"))
    )
    (net (code "55") (name "Net-(IC1-OSC_IN)") (class "Default")
      (node (ref "C16") (pin "1") (pinfunction "1_1") (pintype "passive"))
      (node (ref "IC1") (pin "5") (pinfunction "OSC_IN_5") (pintype "input"))
      (node (ref "P1") (pin "1") (pinfunction "1_1") (pintype "passive"))
      (node (ref "Y1") (pin "2") (pinfunction "OSC2_2") (pintype "passive"))
    )
    (net (code "56") (name "Net-(IC1-OSC_OUT)") (class "Default")
      (node (ref "IC1") (pin "6") (pinfunction "OSC_OUT_6") (pintype "output"))
      (node (ref "P3") (pin "1") (pinfunction "1_1") (pintype "passive"))
      (node (ref "R11") (pin "2") (pinfunction "2_2") (pintype "passive"))
    )
    (net (code "57") (name "Net-(IC1-PA3_-_USART2_RX{slash}TIM5_CH4{slash}ADC12_IN3{slash}TIM2_CH4(7){slash}_ETH_MII_COL)") (class "Default")
      (node (ref "IC1") (pin "17") (pinfunction "PA3_-_USART2_RX/TIM5_CH4/ADC12_IN3/TIM2_CH4(7)/_ETH_MII_COL_17") (pintype "bidirectional"))
      (node (ref "R14") (pin "1") (pinfunction "1_1") (pintype "passive"))
    )
    (net (code "58") (name "Net-(IC1-PC1_-_ADC12_IN11,ETH_MII_MDC,ETH_RMII_MDC)") (class "Default")
      (node (ref "IC1") (pin "9") (pinfunction "PC1_-_ADC12_IN11,ETH_MII_MDC,ETH_RMII_MDC_9") (pintype "bidirectional"))
      (node (ref "R16") (pin "1") (pinfunction "1_1") (pintype "passive"))
    )
    (net (code "59") (name "Net-(IC1-PC15_-_OSC32_OUT)") (class "Default")
      (node (ref "IC1") (pin "4") (pinfunction "PC15_-_OSC32_OUT_4") (pintype "bidirectional"))
      (node (ref "R12") (pin "1") (pinfunction "1_1") (pintype "passive"))
    )
    (net (code "60") (name "Net-(IC2-BS)") (class "Default")
      (node (ref "C15") (pin "1") (pinfunction "1_1") (pintype "passive"))
      (node (ref "IC2") (pin "1") (pinfunction "BS_1") (pintype "passive"))
    )
    (net (code "61") (name "Net-(IC2-COMP)") (class "Default")
      (node (ref "C23") (pin "2") (pinfunction "2_2") (pintype "passive"))
      (node (ref "IC2") (pin "6") (pinfunction "COMP_6") (pintype "passive"))
    )
    (net (code "62") (name "Net-(IC2-FB)") (class "Default")
      (node (ref "IC2") (pin "5") (pinfunction "FB_5") (pintype "input"))
      (node (ref "R8") (pin "1") (pinfunction "1_1") (pintype "passive"))
      (node (ref "R9") (pin "2") (pinfunction "2_2") (pintype "passive"))
    )
    (net (code "63") (name "Net-(IC2-SS)") (class "Default")
      (node (ref "C22") (pin "2") (pinfunction "2_2") (pintype "passive"))
      (node (ref "IC2") (pin "8") (pinfunction "SS_8") (pintype "passive"))
    )
    (net (code "64") (name "Net-(LD1-A)") (class "Default")
      (node (ref "LD1") (pin "1") (pinfunction "A_1") (pintype "passive"))
      (node (ref "R13") (pin "1") (pinfunction "1_1") (pintype "passive"))
    )
    (net (code "65") (name "Net-(LD2-A)") (class "Default")
      (node (ref "LD2") (pin "1") (pinfunction "A_1") (pintype "passive"))
      (node (ref "R14") (pin "2") (pinfunction "2_2") (pintype "passive"))
    )
    (net (code "66") (name "Net-(LD3-A)") (class "Default")
      (node (ref "LD3") (pin "1") (pinfunction "A_1") (pintype "passive"))
      (node (ref "R12") (pin "2") (pinfunction "2_2") (pintype "passive"))
    )
    (net (code "67") (name "Net-(LD4-A)") (class "Default")
      (node (ref "LD4") (pin "1") (pinfunction "A_1") (pintype "passive"))
      (node (ref "R16") (pin "2") (pinfunction "2_2") (pintype "passive"))
    )
    (net (code "68") (name "Net-(LS1--)") (class "Default")
      (node (ref "LS1") (pin "2") (pinfunction "-_2") (pintype "passive"))
      (node (ref "Q1") (pin "3") (pinfunction "C_3") (pintype "passive"))
    )
    (net (code "69") (name "Net-(Q1-B)") (class "Default")
      (node (ref "Q1") (pin "1") (pinfunction "B_1") (pintype "passive"))
      (node (ref "R15") (pin "2") (pinfunction "2_2") (pintype "passive"))
    )
    (net (code "70") (name "Net-(Y1-OSC1)") (class "Default")
      (node (ref "C17") (pin "1") (pinfunction "1_1") (pintype "passive"))
      (node (ref "R11") (pin "1") (pinfunction "1_1") (pintype "passive"))
      (node (ref "Y1") (pin "1") (pinfunction "OSC1_1") (pintype "passive"))
    )
    (net (code "71") (name "unconnected-(IC1-PA6_-_SPI1_MISO{slash}ADC12_IN6_{slash}TIM3_CH1{slash}TIM1_BKIN-Pad22)") (class "Default")
      (node (ref "IC1") (pin "22") (pinfunction "PA6_-_SPI1_MISO/ADC12_IN6_/TIM3_CH1/TIM1_BKIN_22") (pintype "bidirectional"))
    )
    (net (code "72") (name "unconnected-(IC1-PA7_-_SPI1_MOSI{slash}ADC12_IN7{slash}TIM3_CH2{slash}ETH_MII_RX_DV{slash}ETH_RMII_CRS_DV{slash}TIM1_CH1N-Pad23)") (class "Default")
      (node (ref "IC1") (pin "23") (pinfunction "PA7_-_SPI1_MOSI/ADC12_IN7/TIM3_CH2/ETH_MII_RX_DV/ETH_RMII_CRS_DV/TIM1_CH1N_23") (pintype "bidirectional"))
    )
    (net (code "73") (name "unconnected-(IC1-PA9_-_USART1_TX{slash}_TIM1_CH2{slash}OTG_FS_VBUS-Pad42)") (class "Default")
      (node (ref "IC1") (pin "42") (pinfunction "PA9_-_USART1_TX/_TIM1_CH2/OTG_FS_VBUS_42") (pintype "bidirectional"))
    )
    (net (code "74") (name "unconnected-(IC1-PB0_-_ADC12_IN8{slash}TIM3_CH3{slash}ETH_MII_RXD2{slash}TIM1_CH2N-Pad26)") (class "Default")
      (node (ref "IC1") (pin "26") (pinfunction "PB0_-_ADC12_IN8/TIM3_CH3/ETH_MII_RXD2/TIM1_CH2N_26") (pintype "bidirectional"))
    )
    (net (code "75") (name "unconnected-(IC1-PB1_-_ADC12_IN9{slash}TIM3_CH4{slash}ETH_MII_RXD3{slash}TIM1_CH3N-Pad27)") (class "Default")
      (node (ref "IC1") (pin "27") (pinfunction "PB1_-_ADC12_IN9/TIM3_CH4/ETH_MII_RXD3/TIM1_CH3N_27") (pintype "bidirectional"))
    )
    (net (code "76") (name "unconnected-(IC1-PB2_-_PB2{slash}BOOT1-Pad28)") (class "Default")
      (node (ref "IC1") (pin "28") (pinfunction "PB2_-_PB2/BOOT1_28") (pintype "bidirectional"))
    )
    (net (code "77") (name "unconnected-(IC1-PB11_-_I2C2_SDA{slash}USART3_RX{slash}ETH_MII_TX_EN{slash}ETH_RMII_TX_EN{slash}TIM2_CH4-Pad30)") (class "Default")
      (node (ref "IC1") (pin "30") (pinfunction "PB11_-_I2C2_SDA/USART3_RX/ETH_MII_TX_EN/ETH_RMII_TX_EN/TIM2_CH4_30") (pintype "bidirectional"))
    )
    (net (code "78") (name "unconnected-(IC1-PC2_-_ADC12_IN12,__ETH_MII_TXD2-Pad10)") (class "Default")
      (node (ref "IC1") (pin "10") (pinfunction "PC2_-_ADC12_IN12,__ETH_MII_TXD2_10") (pintype "bidirectional"))
    )
    (net (code "79") (name "unconnected-(IC1-PC3_-_ADC12_IN13,_ETH_MII_TX_CLK-Pad11)") (class "Default")
      (node (ref "IC1") (pin "11") (pinfunction "PC3_-_ADC12_IN13,_ETH_MII_TX_CLK_11") (pintype "bidirectional"))
    )
    (net (code "80") (name "unconnected-(IC1-PC6_-__I2S2_MCK{slash}_TIM3_CH1-Pad37)") (class "Default")
      (node (ref "IC1") (pin "37") (pinfunction "PC6_-__I2S2_MCK/_TIM3_CH1_37") (pintype "bidirectional"))
    )
    (net (code "81") (name "unconnected-(IC1-PC7_-__I2S3_MCK{slash}TIM3_CH2-Pad38)") (class "Default")
      (node (ref "IC1") (pin "38") (pinfunction "PC7_-__I2S3_MCK/TIM3_CH2_38") (pintype "bidirectional"))
    )
    (net (code "82") (name "unconnected-(IC1-PC8_-_TIM3_CH3-Pad39)") (class "Default")
      (node (ref "IC1") (pin "39") (pinfunction "PC8_-_TIM3_CH3_39") (pintype "bidirectional"))
    )
    (net (code "83") (name "unconnected-(IC1-PC13_-_TAMPER-RTC-Pad2)") (class "Default")
      (node (ref "IC1") (pin "2") (pinfunction "PC13_-_TAMPER-RTC_2") (pintype "bidirectional"))
    )
    (net (code "84") (name "unconnected-(IC1-PC14_-_OSC32_IN-Pad3)") (class "Default")
      (node (ref "IC1") (pin "3") (pinfunction "PC14_-_OSC32_IN_3") (pintype "bidirectional"))
    )
    (net (code "85") (name "unconnected-(IC1-VBAT-Pad1)") (class "Default")
      (node (ref "IC1") (pin "1") (pinfunction "VBAT_1") (pintype "power_in"))
    )
    (net (code "86") (name "unconnected-(IC2-EN-Pad7)") (class "Default")
      (node (ref "IC2") (pin "7") (pinfunction "EN_7") (pintype "input"))
    )
    (net (code "87") (name "unconnected-(P5-Pad12)") (class "Default")
      (node (ref "P5") (pin "12") (pinfunction "12_12") (pintype "passive"))
    )
    (net (code "88") (name "unconnected-(Z1-NC-Pad2)") (class "Default")
      (node (ref "Z1") (pin "2") (pinfunction "NC_2") (pintype "passive"))
    )
    (net (code "89") (name "unconnected-(Z2-NC-Pad2)") (class "Default")
      (node (ref "Z2") (pin "2") (pinfunction "NC_2") (pintype "passive"))
    )
    (net (code "90") (name "unconnected-(Z3-NC-Pad2)") (class "Default")
      (node (ref "Z3") (pin "2") (pinfunction "NC_2") (pintype "passive"))
    )
    (net (code "91") (name "unconnected-(Z4-NC-Pad2)") (class "Default")
      (node (ref "Z4") (pin "2") (pinfunction "NC_2") (pintype "passive"))
    )
    (net (code "92") (name "unconnected-(Z5-NC-Pad2)") (class "Default")
      (node (ref "Z5") (pin "2") (pinfunction "NC_2") (pintype "passive"))
    )
  )
)
